# Board_1_controller_v1.net
KiCad netlist of a schematic drawn in EAGLE
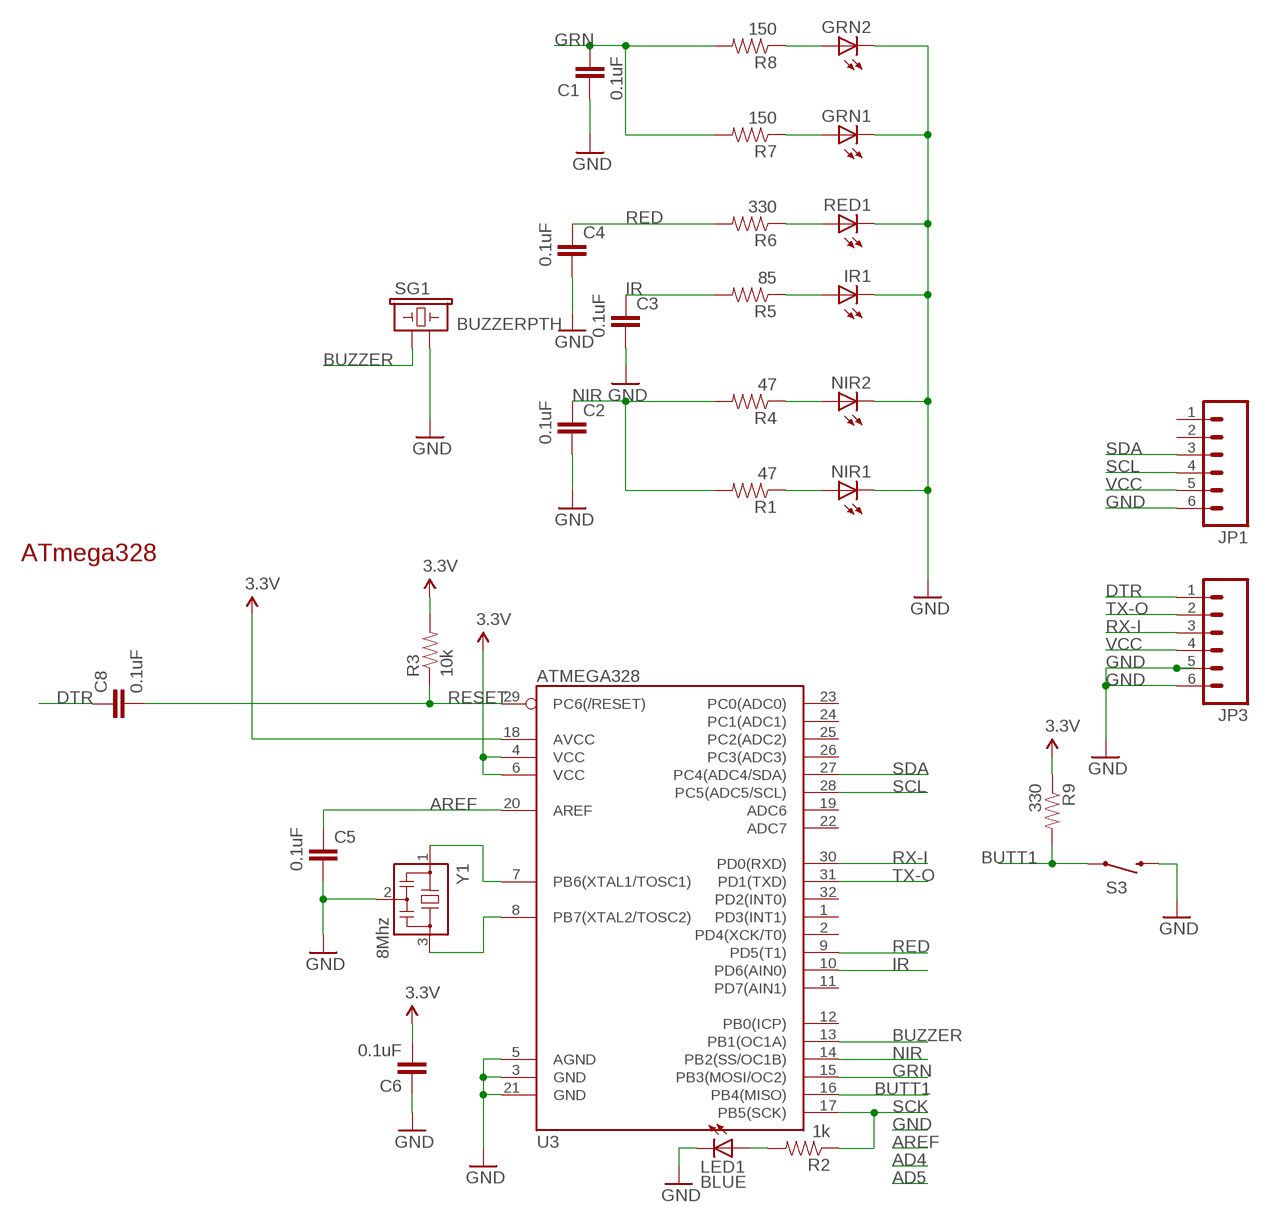
[diagram p0: schematic, sheet 1]

(export (version "E")
  (design (tool "Eeschema 10.0.6"))
  (components
    (comp (ref "C1")
      (value "0.1uF")
      (footprint "eagle-import:0402-CAP")
      (libsource (lib "eagle-import") (part "CAP0402-CAP"))
    )
    (comp (ref "C2")
      (value "0.1uF")
      (footprint "eagle-import:0402-CAP")
      (libsource (lib "eagle-import") (part "CAP0402-CAP"))
    )
    (comp (ref "C3")
      (value "0.1uF")
      (footprint "eagle-import:0402-CAP")
      (libsource (lib "eagle-import") (part "CAP0402-CAP"))
    )
    (comp (ref "C4")
      (value "0.1uF")
      (footprint "eagle-import:0402-CAP")
      (libsource (lib "eagle-import") (part "CAP0402-CAP"))
    )
    (comp (ref "C5")
      (value "0.1uF")
      (footprint "eagle-import:0402-CAP")
      (libsource (lib "eagle-import") (part "CAP0402-CAP"))
    )
    (comp (ref "C6")
      (value "0.1uF")
      (footprint "eagle-import:0402-CAP")
      (libsource (lib "eagle-import") (part "CAP0402-CAP"))
    )
    (comp (ref "C8")
      (value "0.1uF")
      (footprint "eagle-import:0402-CAP")
      (libsource (lib "eagle-import") (part "CAP0402-CAP"))
    )
    (comp (ref "GRN1")
      (value "LED0603")
      (footprint "eagle-import:LED-0603")
      (libsource (lib "eagle-import") (part "LED0603"))
    )
    (comp (ref "GRN2")
      (value "LED0603")
      (footprint "eagle-import:LED-0603")
      (libsource (lib "eagle-import") (part "LED0603"))
    )
    (comp (ref "IR1")
      (value "LED0603")
      (footprint "eagle-import:LED-0603")
      (libsource (lib "eagle-import") (part "LED0603"))
    )
    (comp (ref "JP1")
      (value "M06SMD-1MM")
      (footprint "eagle-import:1X06-1MM")
      (libsource (lib "eagle-import") (part "M06SMD-1MM"))
    )
    (comp (ref "JP3")
      (value "M06SMD-1MM")
      (footprint "eagle-import:1X06-1MM")
      (libsource (lib "eagle-import") (part "M06SMD-1MM"))
    )
    (comp (ref "LED1")
      (value "BLUE")
      (footprint "eagle-import:LED-0603")
      (libsource (lib "eagle-import") (part "SparkFun_LED0603"))
    )
    (comp (ref "NIR1")
      (value "LEDLED1550")
      (footprint "eagle-import:1210")
      (libsource (lib "eagle-import") (part "LED1550LED"))
    )
    (comp (ref "NIR2")
      (value "LEDLED1550")
      (footprint "eagle-import:1210")
      (libsource (lib "eagle-import") (part "LED1550LED"))
    )
    (comp (ref "R1")
      (value "47")
      (footprint "eagle-import:0402-RES")
      (libsource (lib "eagle-import") (part "RESISTOR0402-RES"))
    )
    (comp (ref "R2")
      (value "1k")
      (footprint "eagle-import:0402-RES")
      (libsource (lib "eagle-import") (part "RESISTOR0402-RES"))
    )
    (comp (ref "R3")
      (value "10k")
      (footprint "eagle-import:0402-RES")
      (libsource (lib "eagle-import") (part "RESISTOR0402-RES"))
    )
    (comp (ref "R4")
      (value "47")
      (footprint "eagle-import:0402-RES")
      (libsource (lib "eagle-import") (part "RESISTOR0402-RES"))
    )
    (comp (ref "R5")
      (value "85")
      (footprint "eagle-import:0402-RES")
      (libsource (lib "eagle-import") (part "RESISTOR0402-RES"))
    )
    (comp (ref "R6")
      (value "330")
      (footprint "eagle-import:0402-RES")
      (libsource (lib "eagle-import") (part "RESISTOR0402-RES"))
    )
    (comp (ref "R7")
      (value "150")
      (footprint "eagle-import:0402-RES")
      (libsource (lib "eagle-import") (part "RESISTOR0402-RES"))
    )
    (comp (ref "R8")
      (value "150")
      (footprint "eagle-import:0402-RES")
      (libsource (lib "eagle-import") (part "RESISTOR0402-RES"))
    )
    (comp (ref "R9")
      (value "330")
      (footprint "eagle-import:0402-RES")
      (libsource (lib "eagle-import") (part "RESISTOR0402-RES"))
    )
    (comp (ref "RED1")
      (value "LED0603")
      (footprint "eagle-import:LED-0603")
      (libsource (lib "eagle-import") (part "LED0603"))
    )
    (comp (ref "S3")
      (value "SWITCH-MOMENTARY-2-SMD-1101NE")
      (footprint "eagle-import:TACTILE-SWITCH-1101NE")
      (libsource (lib "eagle-import") (part "SWITCH-MOMENTARY-2-SMD-1101NE"))
    )
    (comp (ref "SG1")
      (value "BUZZERPTH")
      (footprint "eagle-import:BUZZER-12MM")
      (libsource (lib "eagle-import") (part "BUZZERPTH"))
    )
    (comp (ref "U3")
      (value "ATMEGA328")
      (footprint "eagle-import:TQFP32-08")
      (libsource (lib "eagle-import") (part "ATMEGA168"))
    )
    (comp (ref "Y1")
      (value "8Mhz")
      (footprint "eagle-import:CSTCR6M")
      (fields (field (name "MPN") "CSTCR6M00G53-R0"))
      (libsource (lib "eagle-import") (part "CSTCR6M00G53Z"))
    )
  )
  (nets
    (net (code "3") (name "/AREF") (class "Default")
      (node (ref "C5") (pin "1") (pinfunction "1_1") (pintype "passive"))
      (node (ref "U3") (pin "20") (pinfunction "AREF_20") (pintype "bidirectional"))
    )
    (net (code "4") (name "/BUTT1") (class "Default")
      (node (ref "R9") (pin "2") (pinfunction "2_2") (pintype "passive"))
      (node (ref "S3") (pin "P$1") (pinfunction "1_P$1") (pintype "passive"))
      (node (ref "U3") (pin "16") (pinfunction "PB4(MISO)_16") (pintype "bidirectional"))
    )
    (net (code "5") (name "/BUZZER") (class "Default")
      (node (ref "SG1") (pin "+") (pinfunction "1_+") (pintype "passive"))
      (node (ref "U3") (pin "13") (pinfunction "PB1(OC1A)_13") (pintype "bidirectional"))
    )
    (net (code "6") (name "/DTR") (class "Default")
      (node (ref "C8") (pin "1") (pinfunction "1_1") (pintype "passive"))
      (node (ref "JP3") (pin "1") (pinfunction "1_1") (pintype "passive"))
    )
    (net (code "7") (name "/GRN") (class "Default")
      (node (ref "C1") (pin "2") (pinfunction "2_2") (pintype "passive"))
      (node (ref "R7") (pin "2") (pinfunction "2_2") (pintype "passive"))
      (node (ref "R8") (pin "2") (pinfunction "2_2") (pintype "passive"))
      (node (ref "U3") (pin "15") (pinfunction "PB3(MOSI/OC2)_15") (pintype "bidirectional"))
    )
    (net (code "8") (name "/IR") (class "Default")
      (node (ref "C3") (pin "1") (pinfunction "1_1") (pintype "passive"))
      (node (ref "R5") (pin "2") (pinfunction "2_2") (pintype "passive"))
      (node (ref "U3") (pin "10") (pinfunction "PD6(AIN0)_10") (pintype "bidirectional"))
    )
    (net (code "9") (name "/NIR") (class "Default")
      (node (ref "C2") (pin "1") (pinfunction "1_1") (pintype "passive"))
      (node (ref "R1") (pin "2") (pinfunction "2_2") (pintype "passive"))
      (node (ref "R4") (pin "2") (pinfunction "2_2") (pintype "passive"))
      (node (ref "U3") (pin "14") (pinfunction "PB2(SS/OC1B)_14") (pintype "bidirectional"))
    )
    (net (code "10") (name "/RED") (class "Default")
      (node (ref "C4") (pin "1") (pinfunction "1_1") (pintype "passive"))
      (node (ref "R6") (pin "2") (pinfunction "2_2") (pintype "passive"))
      (node (ref "U3") (pin "9") (pinfunction "PD5(T1)_9") (pintype "bidirectional"))
    )
    (net (code "11") (name "/RESET") (class "Default")
      (node (ref "C8") (pin "2") (pinfunction "2_2") (pintype "passive"))
      (node (ref "R3") (pin "1") (pinfunction "1_1") (pintype "passive"))
      (node (ref "U3") (pin "29") (pinfunction "PC6(/RESET)_29") (pintype "bidirectional"))
    )
    (net (code "12") (name "/RX-I") (class "Default")
      (node (ref "JP3") (pin "3") (pinfunction "3_3") (pintype "passive"))
      (node (ref "U3") (pin "30") (pinfunction "PD0(RXD)_30") (pintype "bidirectional"))
    )
    (net (code "13") (name "/SCK") (class "Default")
      (node (ref "R2") (pin "1") (pinfunction "1_1") (pintype "passive"))
      (node (ref "U3") (pin "17") (pinfunction "PB5(SCK)_17") (pintype "bidirectional"))
    )
    (net (code "14") (name "/SCL") (class "Default")
      (node (ref "JP1") (pin "4") (pinfunction "4_4") (pintype "passive"))
      (node (ref "U3") (pin "28") (pinfunction "PC5(ADC5/SCL)_28") (pintype "bidirectional"))
    )
    (net (code "15") (name "/SDA") (class "Default")
      (node (ref "JP1") (pin "3") (pinfunction "3_3") (pintype "passive"))
      (node (ref "U3") (pin "27") (pinfunction "PC4(ADC4/SDA)_27") (pintype "bidirectional"))
    )
    (net (code "16") (name "/TX-O") (class "Default")
      (node (ref "JP3") (pin "2") (pinfunction "2_2") (pintype "passive"))
      (node (ref "U3") (pin "31") (pinfunction "PD1(TXD)_31") (pintype "bidirectional"))
    )
    (net (code "17") (name "3.3V") (class "Default")
      (node (ref "C6") (pin "2") (pinfunction "2_2") (pintype "passive"))
      (node (ref "JP1") (pin "5") (pinfunction "5_5") (pintype "passive"))
      (node (ref "JP3") (pin "4") (pinfunction "4_4") (pintype "passive"))
      (node (ref "R3") (pin "2") (pinfunction "2_2") (pintype "passive"))
      (node (ref "R9") (pin "1") (pinfunction "1_1") (pintype "passive"))
      (node (ref "U3") (pin "18") (pinfunction "AVCC_18") (pintype "bidirectional"))
      (node (ref "U3") (pin "4") (pinfunction "VCC_4") (pintype "bidirectional"))
      (node (ref "U3") (pin "6") (pinfunction "VCC_6") (pintype "bidirectional"))
    )
    (net (code "18") (name "GND") (class "Default")
      (node (ref "C1") (pin "1") (pinfunction "1_1") (pintype "passive"))
      (node (ref "C2") (pin "2") (pinfunction "2_2") (pintype "passive"))
      (node (ref "C3") (pin "2") (pinfunction "2_2") (pintype "passive"))
      (node (ref "C4") (pin "2") (pinfunction "2_2") (pintype "passive"))
      (node (ref "C5") (pin "2") (pinfunction "2_2") (pintype "passive"))
      (node (ref "C6") (pin "1") (pinfunction "1_1") (pintype "passive"))
      (node (ref "GRN1") (pin "C") (pinfunction "C_C") (pintype "passive"))
      (node (ref "GRN2") (pin "C") (pinfunction "C_C") (pintype "passive"))
      (node (ref "IR1") (pin "C") (pinfunction "C_C") (pintype "passive"))
      (node (ref "JP1") (pin "6") (pinfunction "6_6") (pintype "passive"))
      (node (ref "JP3") (pin "5") (pinfunction "5_5") (pintype "passive"))
      (node (ref "JP3") (pin "6") (pinfunction "6_6") (pintype "passive"))
      (node (ref "LED1") (pin "C") (pinfunction "C_C") (pintype "passive"))
      (node (ref "NIR1") (pin "2") (pinfunction "C_2") (pintype "passive"))
      (node (ref "NIR2") (pin "2") (pinfunction "C_2") (pintype "passive"))
      (node (ref "RED1") (pin "C") (pinfunction "C_C") (pintype "passive"))
      (node (ref "S3") (pin "P$2") (pinfunction "2_P$2") (pintype "passive"))
      (node (ref "SG1") (pin "-") (pinfunction "2_-") (pintype "passive"))
      (node (ref "U3") (pin "21") (pinfunction "GND_21") (pintype "bidirectional"))
      (node (ref "U3") (pin "3") (pinfunction "GND_3") (pintype "bidirectional"))
      (node (ref "U3") (pin "5") (pinfunction "AGND_5") (pintype "bidirectional"))
      (node (ref "Y1") (pin "2") (pinfunction "2_2") (pintype "passive"))
    )
    (net (code "19") (name "Net-(GRN1-PadA)") (class "Default")
      (node (ref "GRN1") (pin "A") (pinfunction "A_A") (pintype "passive"))
      (node (ref "R7") (pin "1") (pinfunction "1_1") (pintype "passive"))
    )
    (net (code "20") (name "Net-(GRN2-PadA)") (class "Default")
      (node (ref "GRN2") (pin "A") (pinfunction "A_A") (pintype "passive"))
      (node (ref "R8") (pin "1") (pinfunction "1_1") (pintype "passive"))
    )
    (net (code "21") (name "Net-(IR1-PadA)") (class "Default")
      (node (ref "IR1") (pin "A") (pinfunction "A_A") (pintype "passive"))
      (node (ref "R5") (pin "1") (pinfunction "1_1") (pintype "passive"))
    )
    (net (code "22") (name "Net-(LED1-PadA)") (class "Default")
      (node (ref "LED1") (pin "A") (pinfunction "A_A") (pintype "passive"))
      (node (ref "R2") (pin "2") (pinfunction "2_2") (pintype "passive"))
    )
    (net (code "23") (name "Net-(NIR1-A)") (class "Default")
      (node (ref "NIR1") (pin "1") (pinfunction "A_1") (pintype "passive"))
      (node (ref "R1") (pin "1") (pinfunction "1_1") (pintype "passive"))
    )
    (net (code "24") (name "Net-(NIR2-A)") (class "Default")
      (node (ref "NIR2") (pin "1") (pinfunction "A_1") (pintype "passive"))
      (node (ref "R4") (pin "1") (pinfunction "1_1") (pintype "passive"))
    )
    (net (code "25") (name "Net-(R6-Pad1)") (class "Default")
      (node (ref "R6") (pin "1") (pinfunction "1_1") (pintype "passive"))
      (node (ref "RED1") (pin "A") (pinfunction "A_A") (pintype "passive"))
    )
    (net (code "26") (name "Net-(U3-PB6(XTAL1{slash}TOSC1))") (class "Default")
      (node (ref "U3") (pin "7") (pinfunction "PB6(XTAL1/TOSC1)_7") (pintype "bidirectional"))
      (node (ref "Y1") (pin "1") (pinfunction "1_1") (pintype "passive"))
    )
    (net (code "27") (name "Net-(U3-PB7(XTAL2{slash}TOSC2))") (class "Default")
      (node (ref "U3") (pin "8") (pinfunction "PB7(XTAL2/TOSC2)_8") (pintype "bidirectional"))
      (node (ref "Y1") (pin "3") (pinfunction "3_3") (pintype "passive"))
    )
    (net (code "28") (name "unconnected-(JP1-Pad1)") (class "Default")
      (node (ref "JP1") (pin "1") (pinfunction "1_1") (pintype "passive"))
    )
    (net (code "29") (name "unconnected-(JP1-Pad2)") (class "Default")
      (node (ref "JP1") (pin "2") (pinfunction "2_2") (pintype "passive"))
    )
    (net (code "30") (name "unconnected-(U3-ADC6-Pad19)") (class "Default")
      (node (ref "U3") (pin "19") (pinfunction "ADC6_19") (pintype "bidirectional"))
    )
    (net (code "31") (name "unconnected-(U3-ADC7-Pad22)") (class "Default")
      (node (ref "U3") (pin "22") (pinfunction "ADC7_22") (pintype "bidirectional"))
    )
    (net (code "32") (name "unconnected-(U3-PB0(ICP)-Pad12)") (class "Default")
      (node (ref "U3") (pin "12") (pinfunction "PB0(ICP)_12") (pintype "bidirectional"))
    )
    (net (code "33") (name "unconnected-(U3-PC0(ADC0)-Pad23)") (class "Default")
      (node (ref "U3") (pin "23") (pinfunction "PC0(ADC0)_23") (pintype "bidirectional"))
    )
    (net (code "34") (name "unconnected-(U3-PC1(ADC1)-Pad24)") (class "Default")
      (node (ref "U3") (pin "24") (pinfunction "PC1(ADC1)_24") (pintype "bidirectional"))
    )
    (net (code "35") (name "unconnected-(U3-PC2(ADC2)-Pad25)") (class "Default")
      (node (ref "U3") (pin "25") (pinfunction "PC2(ADC2)_25") (pintype "bidirectional"))
    )
    (net (code "36") (name "unconnected-(U3-PC3(ADC3)-Pad26)") (class "Default")
      (node (ref "U3") (pin "26") (pinfunction "PC3(ADC3)_26") (pintype "bidirectional"))
    )
    (net (code "37") (name "unconnected-(U3-PD2(INT0)-Pad32)") (class "Default")
      (node (ref "U3") (pin "32") (pinfunction "PD2(INT0)_32") (pintype "bidirectional"))
    )
    (net (code "38") (name "unconnected-(U3-PD3(INT1)-Pad1)") (class "Default")
      (node (ref "U3") (pin "1") (pinfunction "PD3(INT1)_1") (pintype "bidirectional"))
    )
    (net (code "39") (name "unconnected-(U3-PD4(XCK{slash}T0)-Pad2)") (class "Default")
      (node (ref "U3") (pin "2") (pinfunction "PD4(XCK/T0)_2") (pintype "bidirectional"))
    )
    (net (code "40") (name "unconnected-(U3-PD7(AIN1)-Pad11)") (class "Default")
      (node (ref "U3") (pin "11") (pinfunction "PD7(AIN1)_11") (pintype "bidirectional"))
    )
  )
)
